# coil_havester_board.net
KiCad netlist of a schematic drawn in EAGLE
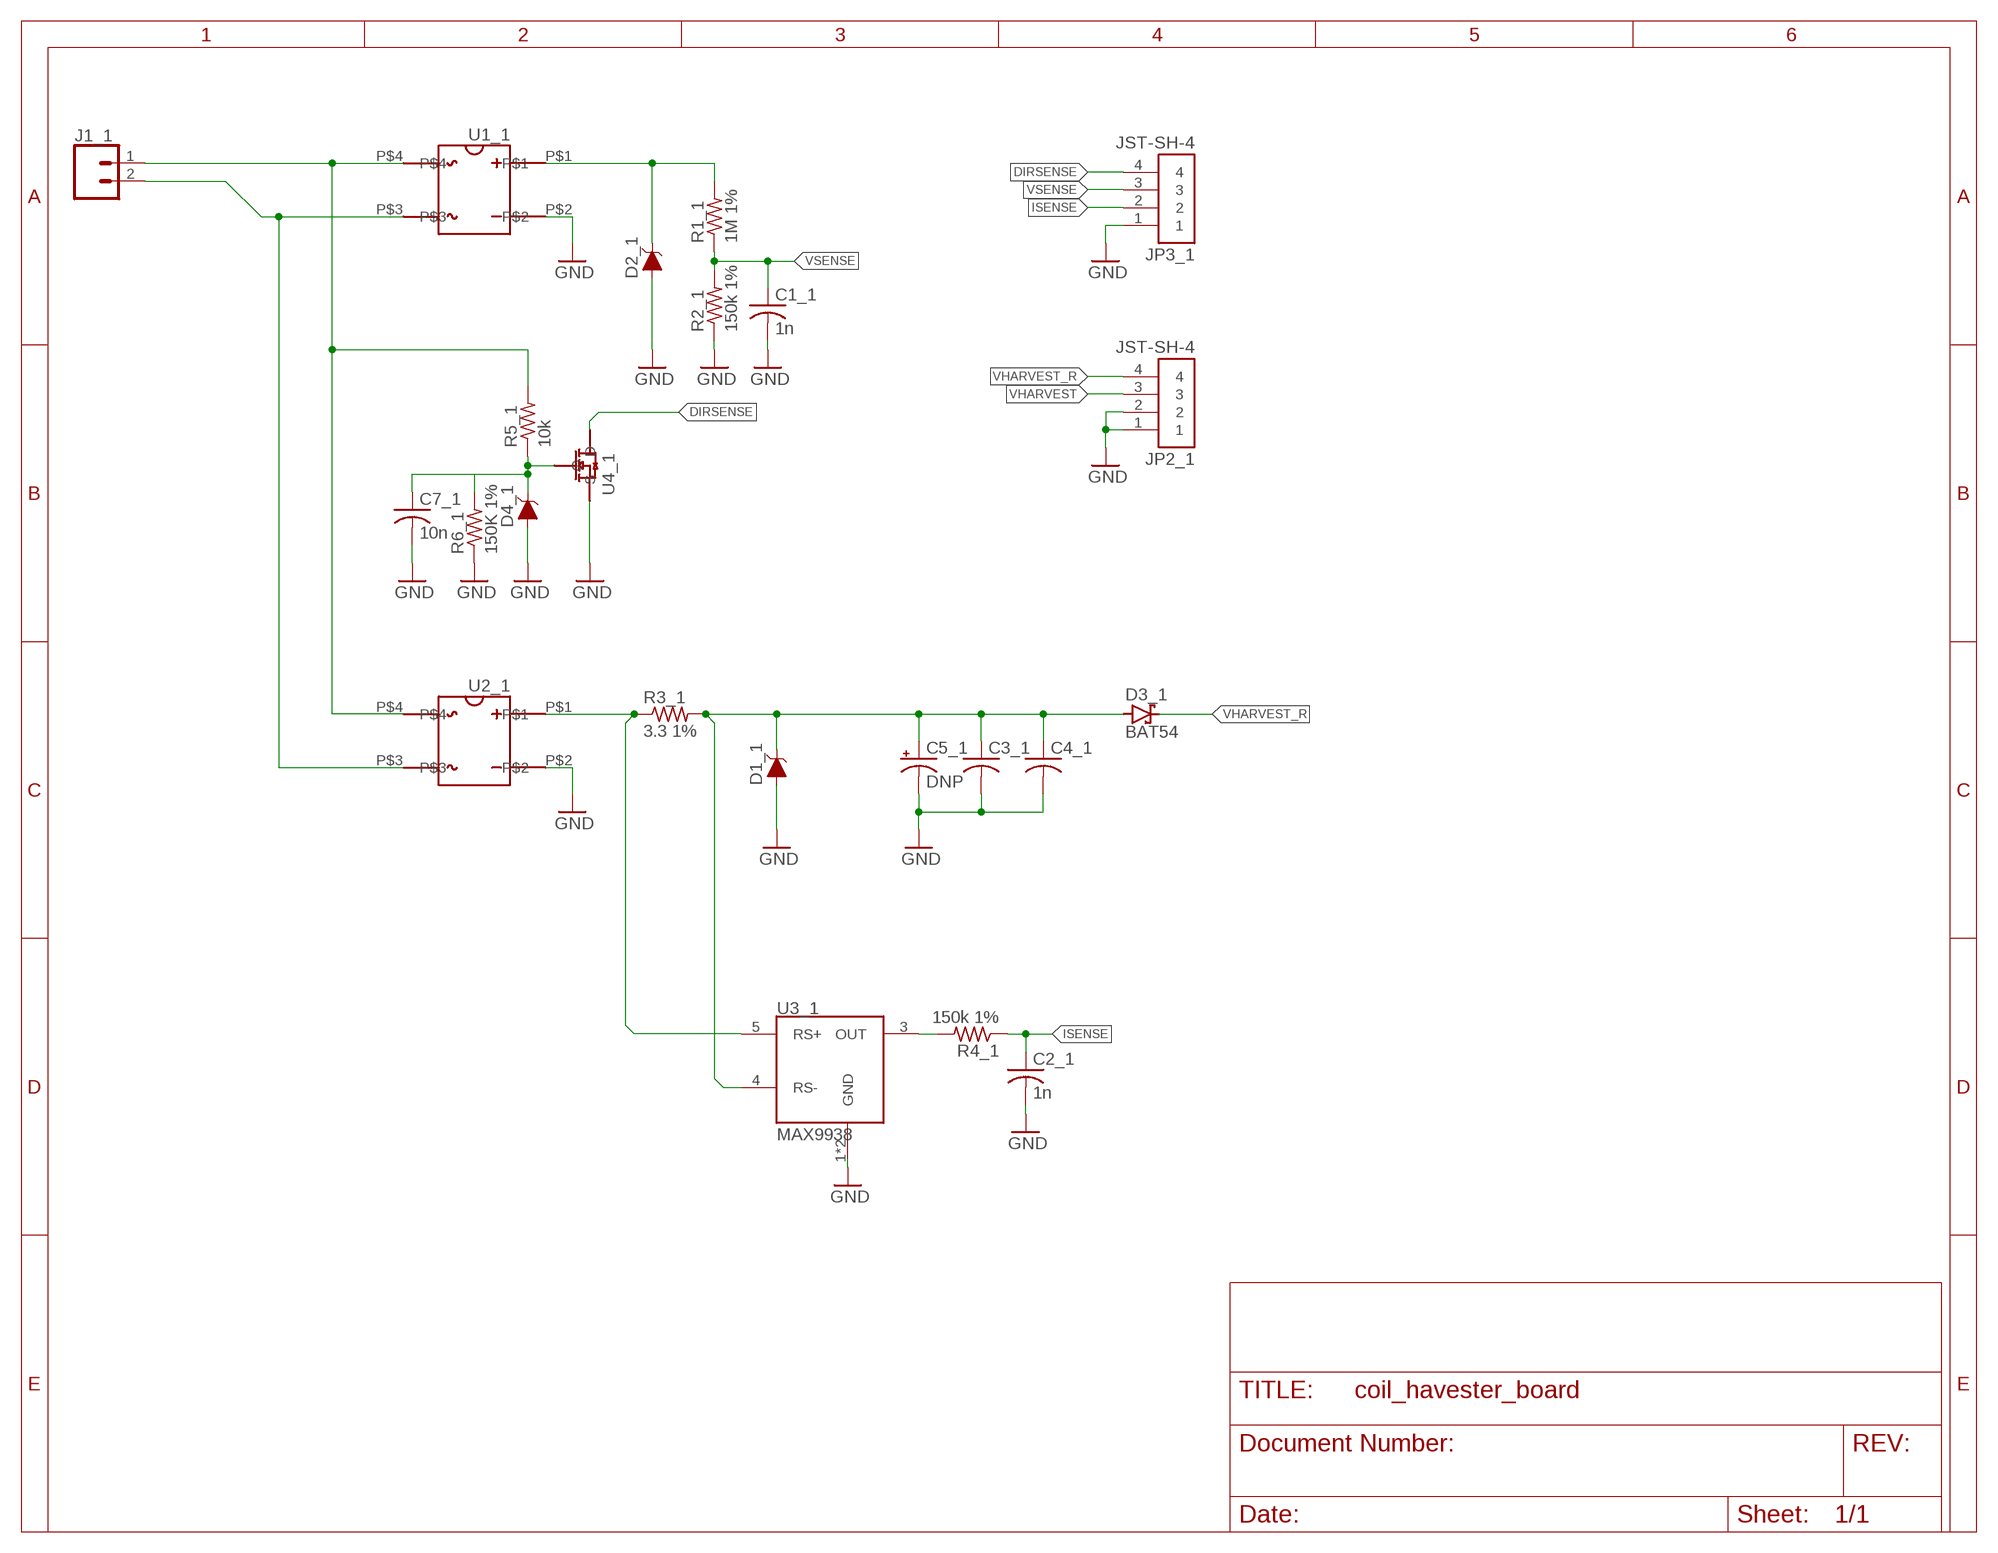
[diagram p0: schematic, sheet 1]

(export (version "E")
  (design (tool "Eeschema 10.0.6"))
  (components
    (comp (ref "C1_1")
      (value "1n")
      (footprint "eagle-import:C0402")
      (fields (field (name "MFR") "SAMSUNG"))
      (libsource (lib "eagle-import") (part "C-USC0402"))
    )
    (comp (ref "C2_1")
      (value "1n")
      (footprint "eagle-import:C0402")
      (fields (field (name "MFR") "SAMSUNG"))
      (libsource (lib "eagle-import") (part "C-USC0402"))
    )
    (comp (ref "C3_1")
      (value "C-USC1206")
      (footprint "eagle-import:C1206")
      (fields (field (name "MFR") "TDK"))
      (libsource (lib "eagle-import") (part "C-USC1206"))
    )
    (comp (ref "C4_1")
      (value "C-USC1206")
      (footprint "eagle-import:C1206")
      (fields (field (name "MFR") "TDK"))
      (libsource (lib "eagle-import") (part "C-USC1206"))
    )
    (comp (ref "C5_1")
      (value "DNP")
      (footprint "eagle-import:E2,5-5")
      (libsource (lib "eagle-import") (part "CPOL-USE2.5-5"))
    )
    (comp (ref "C7_1")
      (value "10n")
      (footprint "eagle-import:C0402")
      (fields (field (name "MFR") "SAMSUNG"))
      (libsource (lib "eagle-import") (part "C-USC0402"))
    )
    (comp (ref "D1_1")
      (value "3.3V")
      (footprint "eagle-import:SOD-323")
      (fields (field (name "MFR") "DIODES_INCORPORATED"))
      (libsource (lib "eagle-import") (part "DIODE-ZENER-MM3Z3V3T1G"))
    )
    (comp (ref "D2_1")
      (value "3.3V")
      (footprint "eagle-import:SOD-323")
      (fields (field (name "MFR") "DIODES_INCORPORATED"))
      (libsource (lib "eagle-import") (part "DIODE-ZENER-MM3Z3V3T1G"))
    )
    (comp (ref "D3_1")
      (value "BAT54")
      (footprint "eagle-import:SOT23")
      (fields (field (name "MFR") "ON"))
      (libsource (lib "eagle-import") (part "BAT54"))
    )
    (comp (ref "D4_1")
      (value "3.3V")
      (footprint "eagle-import:SOD-323")
      (libsource (lib "eagle-import") (part "DIODE-ZENER-MM3Z3V3T1G"))
    )
    (comp (ref "J1_1")
      (value "CONN_02-JST-2MM-SMT")
      (footprint "eagle-import:JST-2-SMD")
      (fields (field (name "MFR") "JST"))
      (libsource (lib "eagle-import") (part "CONN_02-JST-2MM-SMT"))
    )
    (comp (ref "JP2_1")
      (value "JST-SH-4")
      (footprint "eagle-import:JST-SH-4")
      (fields (field (name "MFR") "JST"))
      (libsource (lib "eagle-import") (part "JST-SH-4"))
    )
    (comp (ref "JP3_1")
      (value "JST-SH-4")
      (footprint "eagle-import:JST-SH-4")
      (fields (field (name "MFR") "JST"))
      (libsource (lib "eagle-import") (part "JST-SH-4"))
    )
    (comp (ref "R1_1")
      (value "1M 1%")
      (footprint "eagle-import:R0402")
      (fields (field (name "MFR") "YAGEO"))
      (libsource (lib "eagle-import") (part "R-US_R0402"))
    )
    (comp (ref "R2_1")
      (value "150k 1%")
      (footprint "eagle-import:R0402")
      (fields (field (name "MFR") "YAGEO"))
      (libsource (lib "eagle-import") (part "R-US_R0402"))
    )
    (comp (ref "R3_1")
      (value "3.3 1%")
      (footprint "eagle-import:R0603")
      (fields (field (name "MFR") "PANASONIC"))
      (libsource (lib "eagle-import") (part "R-US_R0603"))
    )
    (comp (ref "R4_1")
      (value "150k 1%")
      (footprint "eagle-import:R0402")
      (fields (field (name "MFR") "YAGEO"))
      (libsource (lib "eagle-import") (part "R-US_R0402"))
    )
    (comp (ref "R5_1")
      (value "10k")
      (footprint "eagle-import:R0402")
      (fields (field (name "MFR") "YAGEO"))
      (libsource (lib "eagle-import") (part "R-US_R0402"))
    )
    (comp (ref "R6_1")
      (value "150K 1%")
      (footprint "eagle-import:R0402")
      (fields (field (name "MFR") "YAGEO"))
      (libsource (lib "eagle-import") (part "R-US_R0402"))
    )
    (comp (ref "U1_1")
      (value "CDBHD140L-G")
      (footprint "eagle-import:CDBHDXX0L-G")
      (fields (field (name "MFR") "COMCHIP"))
      (libsource (lib "eagle-import") (part "CDBHD140L-G"))
    )
    (comp (ref "U2_1")
      (value "CDBHD140L-G")
      (footprint "eagle-import:CDBHDXX0L-G")
      (fields (field (name "MFR") "COMCHIP"))
      (libsource (lib "eagle-import") (part "CDBHD140L-G"))
    )
    (comp (ref "U3_1")
      (value "MAX9938")
      (footprint "eagle-import:SOT23-5")
      (fields (field (name "MFR") "MAXIM"))
      (libsource (lib "eagle-import") (part "MAX9938"))
    )
    (comp (ref "U4_1")
      (value "TN2106K1-G")
      (footprint "eagle-import:TN2106K1-G")
      (fields (field (name "MFR") "MICROCHIP"))
      (libsource (lib "eagle-import") (part "TN2106K1-G"))
    )
  )
  (nets
    (net (code "1") (name "DIRSENSE") (class "Default")
      (node (ref "JP3_1") (pin "4") (pinfunction "4_4") (pintype "bidirectional"))
      (node (ref "U4_1") (pin "D") (pinfunction "D_D") (pintype "bidirectional"))
    )
    (net (code "2") (name "GND") (class "Default")
      (node (ref "C1_1") (pin "2") (pinfunction "2_2") (pintype "passive"))
      (node (ref "C2_1") (pin "2") (pinfunction "2_2") (pintype "passive"))
      (node (ref "C3_1") (pin "2") (pinfunction "2_2") (pintype "passive"))
      (node (ref "C4_1") (pin "2") (pinfunction "2_2") (pintype "passive"))
      (node (ref "C5_1") (pin "-") (pinfunction "-_-") (pintype "passive"))
      (node (ref "C7_1") (pin "2") (pinfunction "2_2") (pintype "passive"))
      (node (ref "D1_1") (pin "A") (pinfunction "A_A") (pintype "passive"))
      (node (ref "D2_1") (pin "A") (pinfunction "A_A") (pintype "passive"))
      (node (ref "D4_1") (pin "A") (pinfunction "A_A") (pintype "passive"))
      (node (ref "JP2_1") (pin "1") (pinfunction "1_1") (pintype "bidirectional"))
      (node (ref "JP2_1") (pin "2") (pinfunction "2_2") (pintype "bidirectional"))
      (node (ref "JP3_1") (pin "1") (pinfunction "1_1") (pintype "bidirectional"))
      (node (ref "R2_1") (pin "1") (pinfunction "1_1") (pintype "passive"))
      (node (ref "R6_1") (pin "1") (pinfunction "1_1") (pintype "passive"))
      (node (ref "U1_1") (pin "P$2") (pinfunction "P$2_P$2") (pintype "bidirectional"))
      (node (ref "U2_1") (pin "P$2") (pinfunction "P$2_P$2") (pintype "bidirectional"))
      (node (ref "U3_1") (pin "1") (pinfunction "GND_1") (pintype "bidirectional"))
      (node (ref "U3_1") (pin "2") (pinfunction "GND_2") (pintype "bidirectional"))
      (node (ref "U4_1") (pin "S") (pinfunction "S_S") (pintype "bidirectional"))
    )
    (net (code "3") (name "ISENSE") (class "Default")
      (node (ref "C2_1") (pin "1") (pinfunction "1_1") (pintype "passive"))
      (node (ref "JP3_1") (pin "2") (pinfunction "2_2") (pintype "bidirectional"))
      (node (ref "R4_1") (pin "1") (pinfunction "1_1") (pintype "passive"))
    )
    (net (code "4") (name "Net-(C7_1-Pad1)") (class "Default")
      (node (ref "C7_1") (pin "1") (pinfunction "1_1") (pintype "passive"))
      (node (ref "D4_1") (pin "C") (pinfunction "C_C") (pintype "passive"))
      (node (ref "R5_1") (pin "1") (pinfunction "1_1") (pintype "passive"))
      (node (ref "R6_1") (pin "2") (pinfunction "2_2") (pintype "passive"))
      (node (ref "U4_1") (pin "G") (pinfunction "G_G") (pintype "bidirectional"))
    )
    (net (code "5") (name "Net-(D2_1-PadC)") (class "Default")
      (node (ref "D2_1") (pin "C") (pinfunction "C_C") (pintype "passive"))
      (node (ref "R1_1") (pin "2") (pinfunction "2_2") (pintype "passive"))
      (node (ref "U1_1") (pin "P$1") (pinfunction "P$1_P$1") (pintype "bidirectional"))
    )
    (net (code "6") (name "Net-(J1_1-1)") (class "Default")
      (node (ref "J1_1") (pin "2") (pinfunction "1_2") (pintype "passive"))
      (node (ref "U1_1") (pin "P$3") (pinfunction "P$3_P$3") (pintype "bidirectional"))
      (node (ref "U2_1") (pin "P$3") (pinfunction "P$3_P$3") (pintype "bidirectional"))
    )
    (net (code "7") (name "Net-(J1_1-2)") (class "Default")
      (node (ref "J1_1") (pin "1") (pinfunction "2_1") (pintype "passive"))
      (node (ref "R5_1") (pin "2") (pinfunction "2_2") (pintype "passive"))
      (node (ref "U1_1") (pin "P$4") (pinfunction "P$4_P$4") (pintype "bidirectional"))
      (node (ref "U2_1") (pin "P$4") (pinfunction "P$4_P$4") (pintype "bidirectional"))
    )
    (net (code "8") (name "Net-(U3_1-OUT)") (class "Default")
      (node (ref "R4_1") (pin "2") (pinfunction "2_2") (pintype "passive"))
      (node (ref "U3_1") (pin "3") (pinfunction "OUT_3") (pintype "bidirectional"))
    )
    (net (code "9") (name "Net-(U3_1-RS+)") (class "Default")
      (node (ref "R3_1") (pin "1") (pinfunction "1_1") (pintype "passive"))
      (node (ref "U2_1") (pin "P$1") (pinfunction "P$1_P$1") (pintype "bidirectional"))
      (node (ref "U3_1") (pin "5") (pinfunction "RS+_5") (pintype "bidirectional"))
    )
    (net (code "10") (name "VHARVEST") (class "Default")
      (node (ref "C3_1") (pin "1") (pinfunction "1_1") (pintype "passive"))
      (node (ref "C4_1") (pin "1") (pinfunction "1_1") (pintype "passive"))
      (node (ref "C5_1") (pin "+") (pinfunction "+_+") (pintype "passive"))
      (node (ref "D1_1") (pin "C") (pinfunction "C_C") (pintype "passive"))
      (node (ref "D3_1") (pin "1") (pinfunction "A_1") (pintype "passive"))
      (node (ref "JP2_1") (pin "3") (pinfunction "3_3") (pintype "bidirectional"))
      (node (ref "R3_1") (pin "2") (pinfunction "2_2") (pintype "passive"))
      (node (ref "U3_1") (pin "4") (pinfunction "RS-_4") (pintype "bidirectional"))
    )
    (net (code "11") (name "VHARVEST_R") (class "Default")
      (node (ref "D3_1") (pin "3") (pinfunction "C_3") (pintype "passive"))
      (node (ref "JP2_1") (pin "4") (pinfunction "4_4") (pintype "bidirectional"))
    )
    (net (code "12") (name "VSENSE") (class "Default")
      (node (ref "C1_1") (pin "1") (pinfunction "1_1") (pintype "passive"))
      (node (ref "JP3_1") (pin "3") (pinfunction "3_3") (pintype "bidirectional"))
      (node (ref "R1_1") (pin "1") (pinfunction "1_1") (pintype "passive"))
      (node (ref "R2_1") (pin "2") (pinfunction "2_2") (pintype "passive"))
    )
  )
)
